# amplificadorAudio.net
KiCad netlist of a schematic drawn in Altium Designer
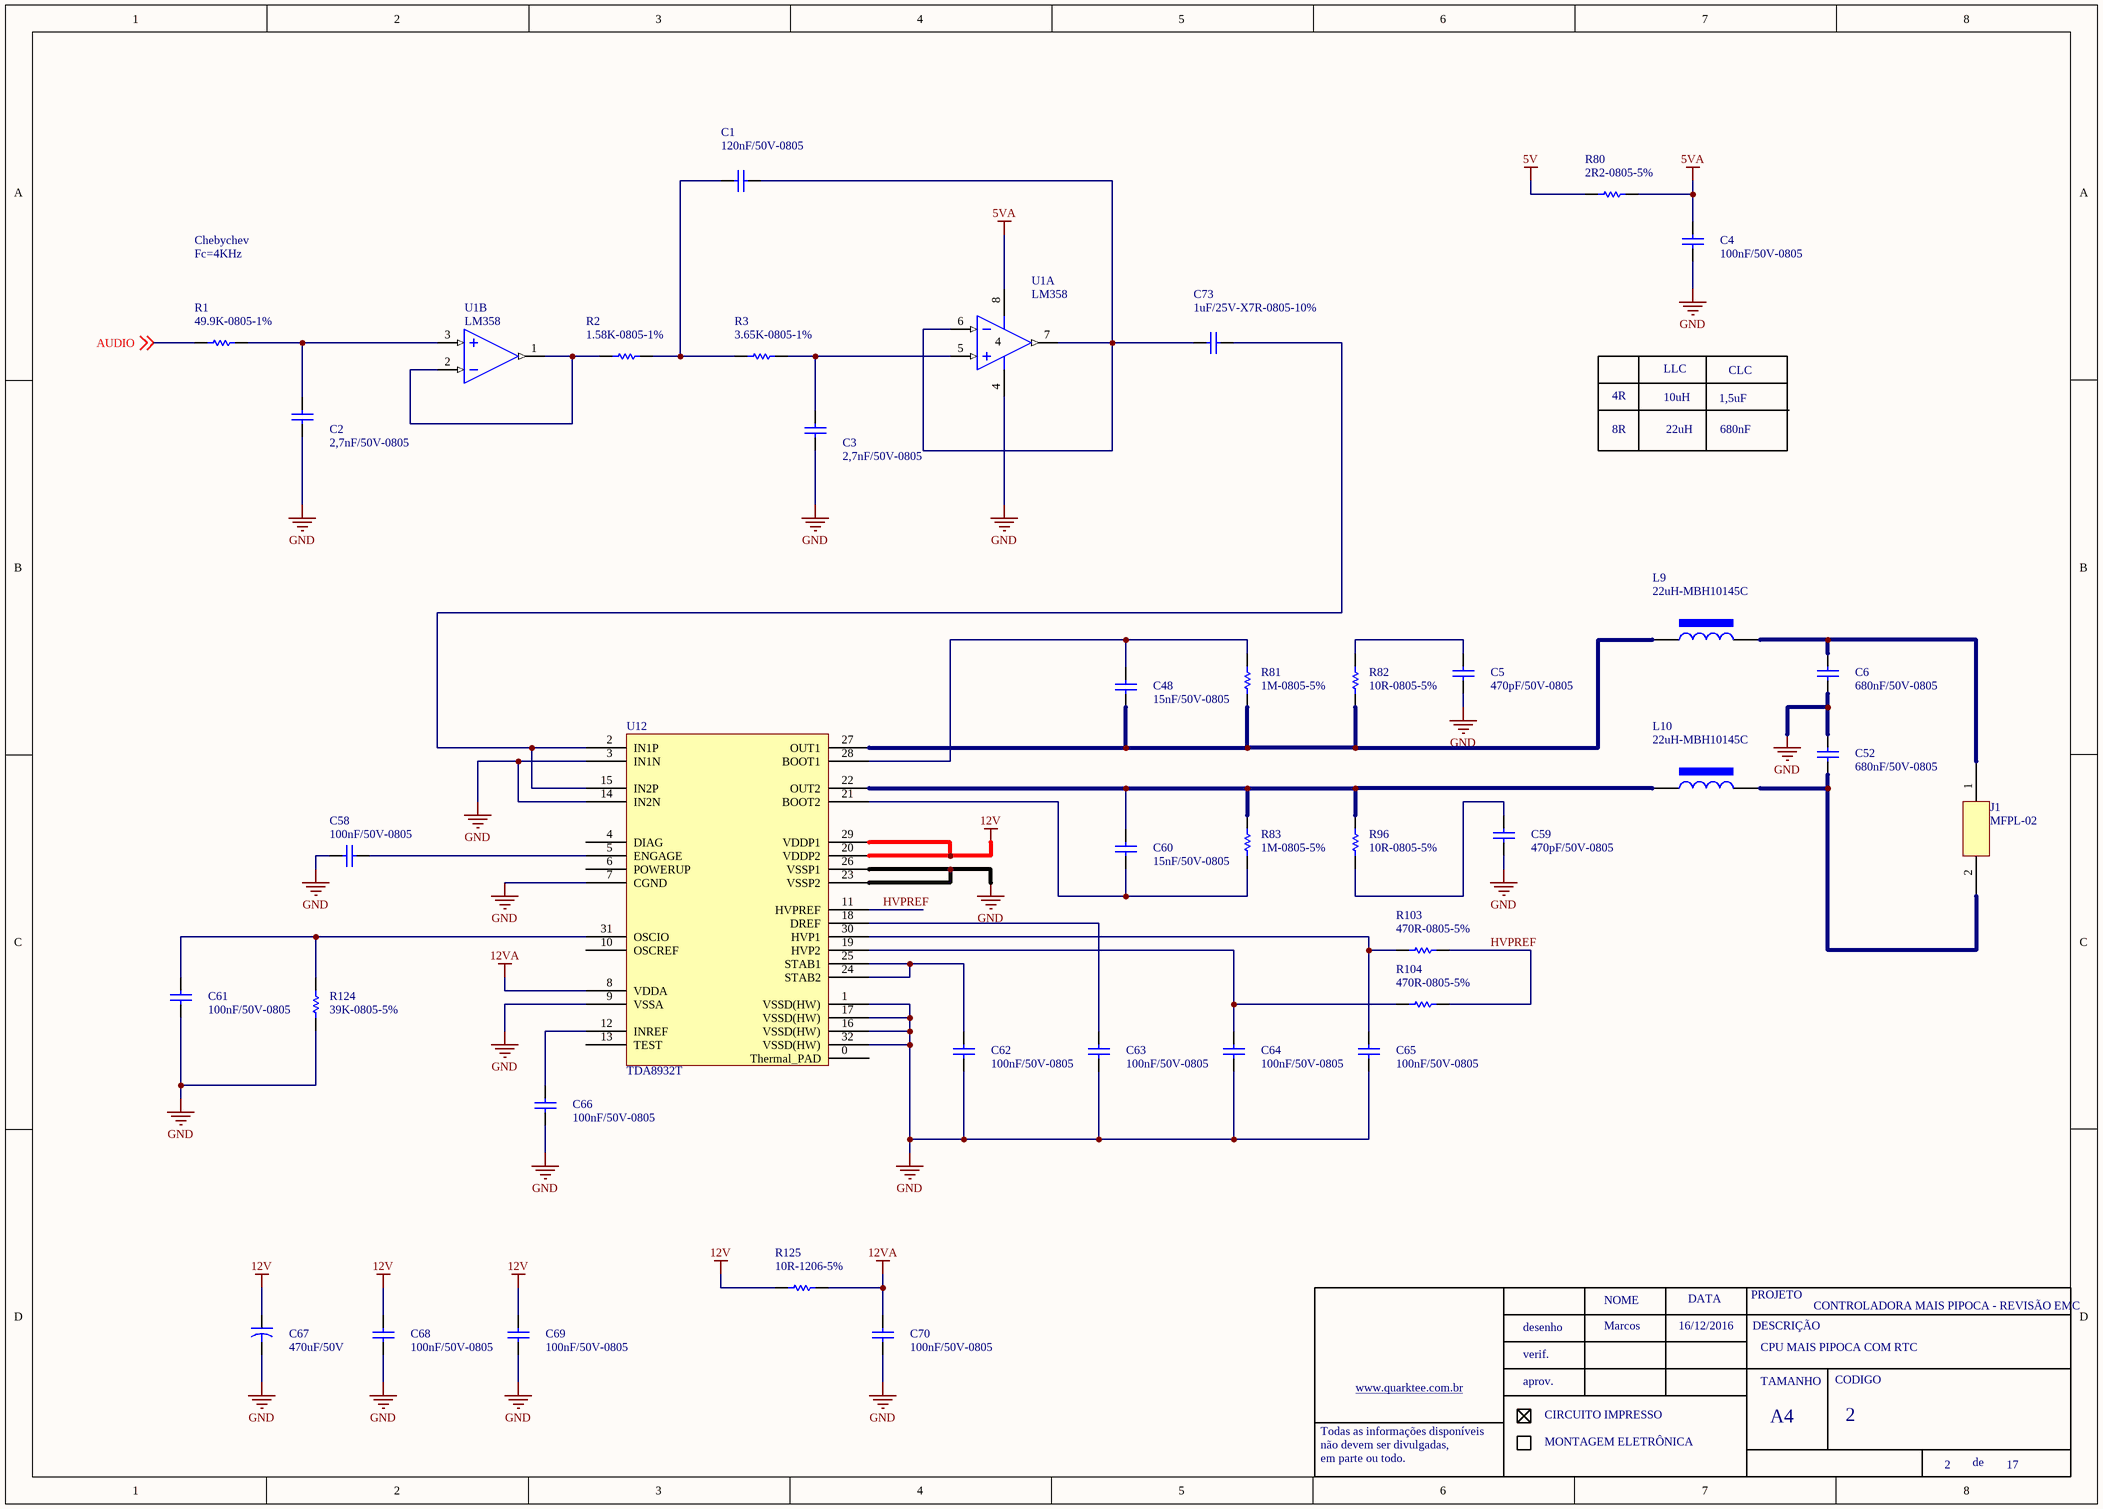
[diagram p0: amplificadorAudio.SchDoc]

(export (version "E")
  (design (tool "Eeschema 10.0.6"))
  (components
    (comp (ref "C1")
      (value "120nF/50V-0805")
      (footprint "0805-REVISADO ONDA")
      (description "100nF/50V-0805")
      (libsource (lib "AquinoLib") (part "100nF/50-0805-NPO"))
    )
    (comp (ref "C2")
      (value "2,7nF/50V-0805")
      (footprint "0805-REVISADO ONDA")
      (description "100nF/50V-0805")
      (libsource (lib "AquinoLib") (part "100nF/50-0805-NPO"))
    )
    (comp (ref "C3")
      (value "2,7nF/50V-0805")
      (footprint "0805-REVISADO ONDA")
      (description "100nF/50V-0805")
      (libsource (lib "AquinoLib") (part "100nF/50-0805-NPO"))
    )
    (comp (ref "C4")
      (value "100nF/50V-0805")
      (footprint "0805-REVISADO ONDA")
      (libsource (lib "AquinoLib") (part "100nF/50-0805-NPO"))
    )
    (comp (ref "C5")
      (value "470pF/50V-0805")
      (footprint "0805-REVISADO ONDA")
      (description "100nF/50V-0805")
      (libsource (lib "AquinoLib") (part "100nF/50-0805-NPO"))
    )
    (comp (ref "C6")
      (value "680nF/50V-0805")
      (footprint "0805-REVISADO ONDA")
      (description "100nF/50V-0805")
      (libsource (lib "AquinoLib") (part "100nF/50-0805-NPO"))
    )
    (comp (ref "C48")
      (value "15nF/50V-0805")
      (footprint "0805-REVISADO ONDA")
      (description "100nF/50V-0805")
      (libsource (lib "AquinoLib") (part "100nF/50-0805-NPO"))
    )
    (comp (ref "C52")
      (value "680nF/50V-0805")
      (footprint "0805-REVISADO ONDA")
      (description "100nF/50V-0805")
      (libsource (lib "AquinoLib") (part "100nF/50-0805-NPO"))
    )
    (comp (ref "C58")
      (value "100nF/50V-0805")
      (footprint "0805-REVISADO ONDA")
      (libsource (lib "AquinoLib") (part "100nF/50-0805-NPO"))
    )
    (comp (ref "C59")
      (value "470pF/50V-0805")
      (footprint "0805-REVISADO ONDA")
      (description "100nF/50V-0805")
      (libsource (lib "AquinoLib") (part "100nF/50-0805-NPO"))
    )
    (comp (ref "C60")
      (value "15nF/50V-0805")
      (footprint "0805-REVISADO ONDA")
      (description "100nF/50V-0805")
      (libsource (lib "AquinoLib") (part "100nF/50-0805-NPO"))
    )
    (comp (ref "C61")
      (value "100nF/50V-0805")
      (footprint "0805-REVISADO ONDA")
      (libsource (lib "AquinoLib") (part "100nF/50-0805-NPO"))
    )
    (comp (ref "C62")
      (value "100nF/50V-0805")
      (footprint "0805-REVISADO ONDA")
      (libsource (lib "AquinoLib") (part "100nF/50-0805-NPO"))
    )
    (comp (ref "C63")
      (value "100nF/50V-0805")
      (footprint "0805-REVISADO ONDA")
      (libsource (lib "AquinoLib") (part "100nF/50-0805-NPO"))
    )
    (comp (ref "C64")
      (value "100nF/50V-0805")
      (footprint "0805-REVISADO ONDA")
      (libsource (lib "AquinoLib") (part "100nF/50-0805-NPO"))
    )
    (comp (ref "C65")
      (value "100nF/50V-0805")
      (footprint "0805-REVISADO ONDA")
      (libsource (lib "AquinoLib") (part "100nF/50-0805-NPO"))
    )
    (comp (ref "C66")
      (value "100nF/50V-0805")
      (footprint "0805-REVISADO ONDA")
      (libsource (lib "AquinoLib") (part "100nF/50-0805-NPO"))
    )
    (comp (ref "C67") (value "470uF/50V") (libsource (lib "AquinoLib") (part "470uF/50V")))
    (comp (ref "C68")
      (value "100nF/50V-0805")
      (footprint "0805-REVISADO ONDA")
      (libsource (lib "AquinoLib") (part "100nF/50-0805-NPO"))
    )
    (comp (ref "C69")
      (value "100nF/50V-0805")
      (footprint "0805-REVISADO ONDA")
      (libsource (lib "AquinoLib") (part "100nF/50-0805-NPO"))
    )
    (comp (ref "C70")
      (value "100nF/50V-0805")
      (footprint "0805-REVISADO ONDA")
      (libsource (lib "AquinoLib") (part "100nF/50-0805-NPO"))
    )
    (comp (ref "C73")
      (value "1uF/25V-X7R-0805-10%")
      (footprint "0805-REVISADO ONDA")
      (description "100nF/50V-0805")
      (libsource (lib "AquinoLib") (part "100nF/50-0805-NPO"))
    )
    (comp (ref "J1") (value "MFPL-02") (footprint "MFPL-02") (libsource (lib "AquinoLib") (part "MFPL-02")))
    (comp (ref "L9")
      (value "22uH-MBH10145C")
      (description "1mH-CNF15-26 AWG")
      (libsource (lib "AquinoLib") (part "indutor 1mH CNF15"))
    )
    (comp (ref "L10")
      (value "22uH-MBH10145C")
      (description "1mH-CNF15-26 AWG")
      (libsource (lib "AquinoLib") (part "indutor 1mH CNF15"))
    )
    (comp (ref "R1")
      (value "49.9K-0805-1%")
      (footprint "0805-REVISADO ONDA")
      (description "10K-0805-5%")
      (libsource (lib "AquinoLib") (part "10K-0805-5%"))
    )
    (comp (ref "R2")
      (value "1.58K-0805-1%")
      (footprint "0805-REVISADO ONDA")
      (description "10K-0805-5%")
      (libsource (lib "AquinoLib") (part "10K-0805-5%"))
    )
    (comp (ref "R3")
      (value "3.65K-0805-1%")
      (footprint "0805-REVISADO ONDA")
      (description "10K-0805-5%")
      (libsource (lib "AquinoLib") (part "10K-0805-5%"))
    )
    (comp (ref "R80")
      (value "2R2-0805-5%")
      (description "10R-0805-5%")
      (libsource (lib "AquinoLib") (part "10R-0805-5%"))
    )
    (comp (ref "R81")
      (value "1M-0805-5%")
      (footprint "0805-REVISADO ONDA")
      (description "10K-0805-5%")
      (libsource (lib "AquinoLib") (part "10K-0805-5%"))
    )
    (comp (ref "R82")
      (value "10R-0805-5%")
      (footprint "0805-REVISADO ONDA")
      (description "10K-0805-5%")
      (libsource (lib "AquinoLib") (part "10K-0805-5%"))
    )
    (comp (ref "R83")
      (value "1M-0805-5%")
      (footprint "0805-REVISADO ONDA")
      (description "10K-0805-5%")
      (libsource (lib "AquinoLib") (part "10K-0805-5%"))
    )
    (comp (ref "R96")
      (value "10R-0805-5%")
      (footprint "0805-REVISADO ONDA")
      (description "10K-0805-5%")
      (libsource (lib "AquinoLib") (part "10K-0805-5%"))
    )
    (comp (ref "R103")
      (value "470R-0805-5%")
      (footprint "0805-REVISADO ONDA")
      (description "10K-0805-5%")
      (libsource (lib "AquinoLib") (part "10K-0805-5%"))
    )
    (comp (ref "R104")
      (value "470R-0805-5%")
      (footprint "0805-REVISADO ONDA")
      (description "10K-0805-5%")
      (libsource (lib "AquinoLib") (part "10K-0805-5%"))
    )
    (comp (ref "R124")
      (value "39K-0805-5%")
      (footprint "0805-REVISADO ONDA")
      (description "10K-0805-5%")
      (libsource (lib "AquinoLib") (part "10K-0805-5%"))
    )
    (comp (ref "R125")
      (value "10R-1206-5%")
      (description "10R-0805-5%")
      (libsource (lib "AquinoLib") (part "10R-0805-5%"))
    )
    (comp (ref "U1") (value "LM358") (libsource (lib "AquinoLib") (part "LM358")))
    (comp (ref "U12") (value "TDA8932T") (libsource (lib "AquinoLib") (part "TDA8932T")))
  )
  (nets
    (net (code "1") (name "/HVPREF") (class "Default")
      (node (ref "R103") (pin "1") (pinfunction "1_1") (pintype "passive"))
      (node (ref "R104") (pin "1") (pinfunction "1_1") (pintype "passive"))
      (node (ref "U12") (pin "11") (pinfunction "HVPREF_11") (pintype "passive"))
    )
    (net (code "2") (name "5V") (class "Default")
      (node (ref "R80") (pin "1") (pinfunction "1_1") (pintype "passive"))
    )
    (net (code "3") (name "5VA") (class "Default")
      (node (ref "C4") (pin "2") (pinfunction "2_2") (pintype "passive"))
      (node (ref "R80") (pin "2") (pinfunction "2_2") (pintype "passive"))
      (node (ref "U1") (pin "8") (pinfunction "V+_8") (pintype "power_in"))
    )
    (net (code "4") (name "12V") (class "Default")
      (node (ref "C67") (pin "1") (pinfunction "1_1") (pintype "passive"))
      (node (ref "C68") (pin "2") (pinfunction "2_2") (pintype "passive"))
      (node (ref "C69") (pin "2") (pinfunction "2_2") (pintype "passive"))
      (node (ref "R125") (pin "1") (pinfunction "1_1") (pintype "passive"))
      (node (ref "U12") (pin "20") (pinfunction "VDDP2_20") (pintype "passive"))
      (node (ref "U12") (pin "29") (pinfunction "VDDP1_29") (pintype "passive"))
    )
    (net (code "5") (name "12VA") (class "Default")
      (node (ref "C70") (pin "2") (pinfunction "2_2") (pintype "passive"))
      (node (ref "R125") (pin "2") (pinfunction "2_2") (pintype "passive"))
      (node (ref "U12") (pin "8") (pinfunction "VDDA_8") (pintype "passive"))
    )
    (net (code "6") (name "AUDIO") (class "Default")
      (node (ref "R1") (pin "1") (pinfunction "1_1") (pintype "passive"))
    )
    (net (code "7") (name "GND") (class "Default")
      (node (ref "C2") (pin "1") (pinfunction "1_1") (pintype "passive"))
      (node (ref "C3") (pin "1") (pinfunction "1_1") (pintype "passive"))
      (node (ref "C4") (pin "1") (pinfunction "1_1") (pintype "passive"))
      (node (ref "C5") (pin "1") (pinfunction "1_1") (pintype "passive"))
      (node (ref "C52") (pin "2") (pinfunction "2_2") (pintype "passive"))
      (node (ref "C58") (pin "2") (pinfunction "2_2") (pintype "passive"))
      (node (ref "C59") (pin "1") (pinfunction "1_1") (pintype "passive"))
      (node (ref "C6") (pin "1") (pinfunction "1_1") (pintype "passive"))
      (node (ref "C61") (pin "1") (pinfunction "1_1") (pintype "passive"))
      (node (ref "C62") (pin "1") (pinfunction "1_1") (pintype "passive"))
      (node (ref "C63") (pin "1") (pinfunction "1_1") (pintype "passive"))
      (node (ref "C64") (pin "1") (pinfunction "1_1") (pintype "passive"))
      (node (ref "C65") (pin "1") (pinfunction "1_1") (pintype "passive"))
      (node (ref "C66") (pin "1") (pinfunction "1_1") (pintype "passive"))
      (node (ref "C67") (pin "2") (pinfunction "2_2") (pintype "passive"))
      (node (ref "C68") (pin "1") (pinfunction "1_1") (pintype "passive"))
      (node (ref "C69") (pin "1") (pinfunction "1_1") (pintype "passive"))
      (node (ref "C70") (pin "1") (pinfunction "1_1") (pintype "passive"))
      (node (ref "R124") (pin "1") (pinfunction "1_1") (pintype "passive"))
      (node (ref "U1") (pin "4") (pinfunction "GND_4") (pintype "power_in"))
      (node (ref "U12") (pin "1") (pinfunction "VSSD(HW)_1") (pintype "passive"))
      (node (ref "U12") (pin "14") (pinfunction "IN2N_14") (pintype "passive"))
      (node (ref "U12") (pin "16") (pinfunction "VSSD(HW)_16") (pintype "passive"))
      (node (ref "U12") (pin "17") (pinfunction "VSSD(HW)_17") (pintype "passive"))
      (node (ref "U12") (pin "23") (pinfunction "VSSP2_23") (pintype "passive"))
      (node (ref "U12") (pin "26") (pinfunction "VSSP1_26") (pintype "passive"))
      (node (ref "U12") (pin "3") (pinfunction "IN1N_3") (pintype "passive"))
      (node (ref "U12") (pin "32") (pinfunction "VSSD(HW)_32") (pintype "passive"))
      (node (ref "U12") (pin "7") (pinfunction "CGND_7") (pintype "passive"))
      (node (ref "U12") (pin "9") (pinfunction "VSSA_9") (pintype "passive"))
    )
    (net (code "8") (name "Net-(C1-Pad2)") (class "Default")
      (node (ref "C1") (pin "2") (pinfunction "2_2") (pintype "passive"))
      (node (ref "R2") (pin "2") (pinfunction "2_2") (pintype "passive"))
      (node (ref "R3") (pin "1") (pinfunction "1_1") (pintype "passive"))
    )
    (net (code "9") (name "Net-(C5-Pad2)") (class "Default")
      (node (ref "C5") (pin "2") (pinfunction "2_2") (pintype "passive"))
      (node (ref "R82") (pin "1") (pinfunction "1_1") (pintype "passive"))
    )
    (net (code "10") (name "Net-(C6-Pad2)") (class "Default")
      (node (ref "C6") (pin "2") (pinfunction "2_2") (pintype "passive"))
      (node (ref "J1") (pin "1") (pinfunction "1_1") (pintype "passive"))
      (node (ref "L9") (pin "1") (pinfunction "1_1") (pintype "passive"))
    )
    (net (code "11") (name "Net-(C52-Pad1)") (class "Default")
      (node (ref "C52") (pin "1") (pinfunction "1_1") (pintype "passive"))
      (node (ref "J1") (pin "2") (pinfunction "2_2") (pintype "passive"))
      (node (ref "L10") (pin "1") (pinfunction "1_1") (pintype "passive"))
    )
    (net (code "12") (name "Net-(C59-Pad2)") (class "Default")
      (node (ref "C59") (pin "2") (pinfunction "2_2") (pintype "passive"))
      (node (ref "R96") (pin "2") (pinfunction "2_2") (pintype "passive"))
    )
    (net (code "13") (name "Net-(U1A-IN+)") (class "Default")
      (node (ref "C3") (pin "2") (pinfunction "2_2") (pintype "passive"))
      (node (ref "R3") (pin "2") (pinfunction "2_2") (pintype "passive"))
      (node (ref "U1") (pin "5") (pinfunction "IN+_5") (pintype "input"))
    )
    (net (code "14") (name "Net-(U1A-IN-)") (class "Default")
      (node (ref "C1") (pin "1") (pinfunction "1_1") (pintype "passive"))
      (node (ref "C73") (pin "2") (pinfunction "2_2") (pintype "passive"))
      (node (ref "U1") (pin "6") (pinfunction "IN-_6") (pintype "input"))
      (node (ref "U1") (pin "7") (pinfunction "OUT_7") (pintype "output"))
    )
    (net (code "15") (name "Net-(U1B-IN+)") (class "Default")
      (node (ref "C2") (pin "2") (pinfunction "2_2") (pintype "passive"))
      (node (ref "R1") (pin "2") (pinfunction "2_2") (pintype "passive"))
      (node (ref "U1") (pin "3") (pinfunction "IN+_3") (pintype "input"))
    )
    (net (code "16") (name "Net-(U1B-IN-)") (class "Default")
      (node (ref "R2") (pin "1") (pinfunction "1_1") (pintype "passive"))
      (node (ref "U1") (pin "1") (pinfunction "OUT_1") (pintype "output"))
      (node (ref "U1") (pin "2") (pinfunction "IN-_2") (pintype "input"))
    )
    (net (code "17") (name "Net-(U12-BOOT1)") (class "Default")
      (node (ref "C48") (pin "2") (pinfunction "2_2") (pintype "passive"))
      (node (ref "R81") (pin "1") (pinfunction "1_1") (pintype "passive"))
      (node (ref "U12") (pin "28") (pinfunction "BOOT1_28") (pintype "passive"))
    )
    (net (code "18") (name "Net-(U12-BOOT2)") (class "Default")
      (node (ref "C60") (pin "1") (pinfunction "1_1") (pintype "passive"))
      (node (ref "R83") (pin "2") (pinfunction "2_2") (pintype "passive"))
      (node (ref "U12") (pin "21") (pinfunction "BOOT2_21") (pintype "passive"))
    )
    (net (code "19") (name "Net-(U12-DREF)") (class "Default")
      (node (ref "C63") (pin "2") (pinfunction "2_2") (pintype "passive"))
      (node (ref "U12") (pin "18") (pinfunction "DREF_18") (pintype "passive"))
    )
    (net (code "20") (name "Net-(U12-ENGAGE)") (class "Default")
      (node (ref "C58") (pin "1") (pinfunction "1_1") (pintype "passive"))
      (node (ref "U12") (pin "5") (pinfunction "ENGAGE_5") (pintype "passive"))
    )
    (net (code "21") (name "Net-(U12-HVP1)") (class "Default")
      (node (ref "C65") (pin "2") (pinfunction "2_2") (pintype "passive"))
      (node (ref "R103") (pin "2") (pinfunction "2_2") (pintype "passive"))
      (node (ref "U12") (pin "30") (pinfunction "HVP1_30") (pintype "passive"))
    )
    (net (code "22") (name "Net-(U12-HVP2)") (class "Default")
      (node (ref "C64") (pin "2") (pinfunction "2_2") (pintype "passive"))
      (node (ref "R104") (pin "2") (pinfunction "2_2") (pintype "passive"))
      (node (ref "U12") (pin "19") (pinfunction "HVP2_19") (pintype "passive"))
    )
    (net (code "23") (name "Net-(U12-IN1P)") (class "Default")
      (node (ref "C73") (pin "1") (pinfunction "1_1") (pintype "passive"))
      (node (ref "U12") (pin "15") (pinfunction "IN2P_15") (pintype "passive"))
      (node (ref "U12") (pin "2") (pinfunction "IN1P_2") (pintype "passive"))
    )
    (net (code "24") (name "Net-(U12-INREF)") (class "Default")
      (node (ref "C66") (pin "2") (pinfunction "2_2") (pintype "passive"))
      (node (ref "U12") (pin "12") (pinfunction "INREF_12") (pintype "passive"))
    )
    (net (code "25") (name "Net-(U12-OSCIO)") (class "Default")
      (node (ref "C61") (pin "2") (pinfunction "2_2") (pintype "passive"))
      (node (ref "R124") (pin "2") (pinfunction "2_2") (pintype "passive"))
      (node (ref "U12") (pin "31") (pinfunction "OSCIO_31") (pintype "passive"))
    )
    (net (code "26") (name "Net-(U12-OUT1)") (class "Default")
      (node (ref "C48") (pin "1") (pinfunction "1_1") (pintype "passive"))
      (node (ref "L9") (pin "2") (pinfunction "2_2") (pintype "passive"))
      (node (ref "R81") (pin "2") (pinfunction "2_2") (pintype "passive"))
      (node (ref "R82") (pin "2") (pinfunction "2_2") (pintype "passive"))
      (node (ref "U12") (pin "27") (pinfunction "OUT1_27") (pintype "passive"))
    )
    (net (code "27") (name "Net-(U12-OUT2)") (class "Default")
      (node (ref "C60") (pin "2") (pinfunction "2_2") (pintype "passive"))
      (node (ref "L10") (pin "2") (pinfunction "2_2") (pintype "passive"))
      (node (ref "R83") (pin "1") (pinfunction "1_1") (pintype "passive"))
      (node (ref "R96") (pin "1") (pinfunction "1_1") (pintype "passive"))
      (node (ref "U12") (pin "22") (pinfunction "OUT2_22") (pintype "passive"))
    )
    (net (code "28") (name "Net-(U12-STAB1)") (class "Default")
      (node (ref "C62") (pin "2") (pinfunction "2_2") (pintype "passive"))
      (node (ref "U12") (pin "24") (pinfunction "STAB2_24") (pintype "passive"))
      (node (ref "U12") (pin "25") (pinfunction "STAB1_25") (pintype "passive"))
    )
    (net (code "29") (name "unconnected-(U12-DIAG-Pad4)") (class "Default")
      (node (ref "U12") (pin "4") (pinfunction "DIAG_4") (pintype "passive"))
    )
    (net (code "30") (name "unconnected-(U12-OSCREF-Pad10)") (class "Default")
      (node (ref "U12") (pin "10") (pinfunction "OSCREF_10") (pintype "passive"))
    )
    (net (code "31") (name "unconnected-(U12-POWERUP-Pad6)") (class "Default")
      (node (ref "U12") (pin "6") (pinfunction "POWERUP_6") (pintype "passive"))
    )
    (net (code "32") (name "unconnected-(U12-TEST-Pad13)") (class "Default")
      (node (ref "U12") (pin "13") (pinfunction "TEST_13") (pintype "passive"))
    )
    (net (code "33") (name "unconnected-(U12-Thermal_PAD-Pad0)") (class "Default")
      (node (ref "U12") (pin "0") (pinfunction "Thermal_PAD_0") (pintype "passive"))
    )
  )
)
